# jamma.net
KiCad netlist of a schematic drawn in EAGLE
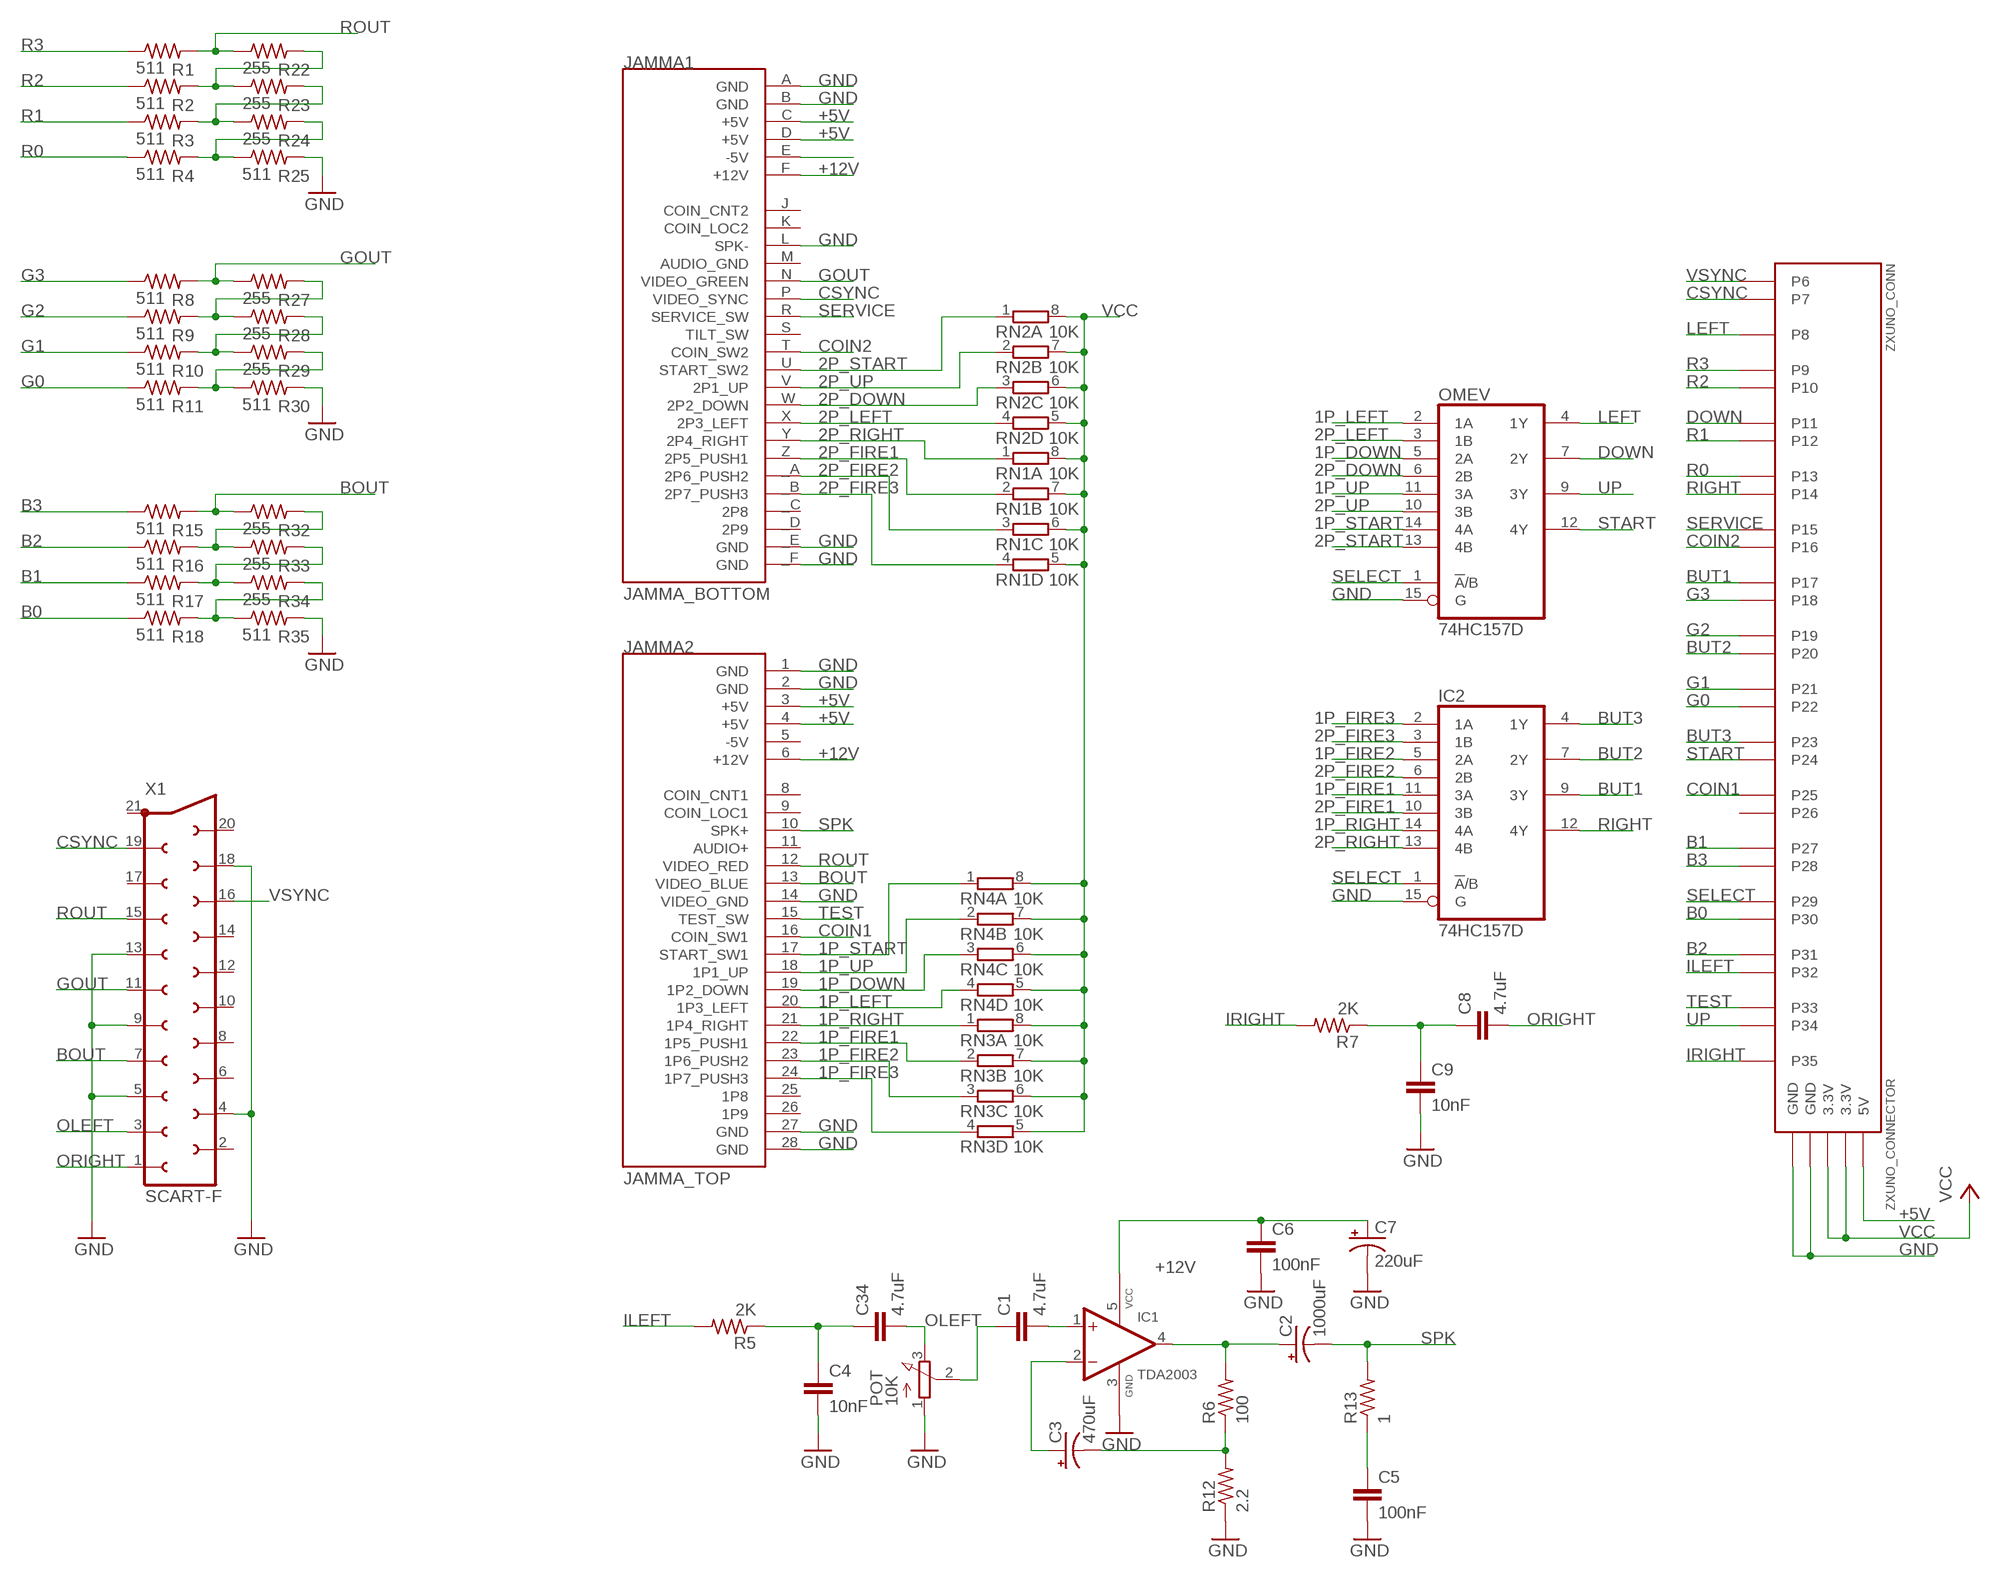
[diagram p0: schematic, sheet 1]

(export (version "E")
  (design (tool "Eeschema 10.0.6"))
  (components
    (comp (ref "C1")
      (value "4.7uF")
      (footprint "eagle-import:C0805")
      (libsource (lib "eagle-import") (part "C-EUC0805"))
    )
    (comp (ref "C2")
      (value "1000uF")
      (footprint "eagle-import:E5-13")
      (libsource (lib "eagle-import") (part "CPOL-USE5-13"))
    )
    (comp (ref "C3")
      (value "470uF")
      (footprint "eagle-import:E5-10,5")
      (libsource (lib "eagle-import") (part "CPOL-USE5-10.5"))
    )
    (comp (ref "C4")
      (value "10nF")
      (footprint "eagle-import:C0805")
      (libsource (lib "eagle-import") (part "C-EUC0805"))
    )
    (comp (ref "C5")
      (value "100nF")
      (footprint "eagle-import:C0805K")
      (libsource (lib "eagle-import") (part "C-EUC0805K"))
    )
    (comp (ref "C6")
      (value "100nF")
      (footprint "eagle-import:C0805K")
      (libsource (lib "eagle-import") (part "C-EUC0805K"))
    )
    (comp (ref "C7")
      (value "220uF")
      (footprint "eagle-import:E5-10,5")
      (libsource (lib "eagle-import") (part "CPOL-USE5-10.5"))
    )
    (comp (ref "C8")
      (value "4.7uF")
      (footprint "eagle-import:C0805")
      (libsource (lib "eagle-import") (part "C-EUC0805"))
    )
    (comp (ref "C9")
      (value "10nF")
      (footprint "eagle-import:C0805")
      (libsource (lib "eagle-import") (part "C-EUC0805"))
    )
    (comp (ref "C34")
      (value "4.7uF")
      (footprint "eagle-import:C0805")
      (libsource (lib "eagle-import") (part "C-EUC0805"))
    )
    (comp (ref "IC1")
      (value "TDA2003")
      (footprint "eagle-import:PENTAWATT-V")
      (libsource (lib "eagle-import") (part "TDA2003"))
    )
    (comp (ref "IC2")
      (value "74HC157D")
      (footprint "eagle-import:SO16")
      (libsource (lib "eagle-import") (part "74157DHC"))
    )
    (comp (ref "JAMMA1")
      (value "JAMMA_BOTTOM")
      (footprint "eagle-import:JAMMA_BOTTOM")
      (libsource (lib "eagle-import") (part "JAMMA_BOTTOM"))
    )
    (comp (ref "JAMMA2")
      (value "JAMMA_TOP")
      (footprint "eagle-import:JAMMA_TOP")
      (libsource (lib "eagle-import") (part "JAMMA_TOP"))
    )
    (comp (ref "OMEV")
      (value "74HC157D")
      (footprint "eagle-import:SO16")
      (libsource (lib "eagle-import") (part "74157DHC"))
    )
    (comp (ref "POT")
      (value "10K")
      (footprint "eagle-import:POT")
      (libsource (lib "eagle-import") (part "POT"))
    )
    (comp (ref "R1")
      (value "511")
      (footprint "eagle-import:R0805")
      (libsource (lib "eagle-import") (part "R-US_R0805"))
    )
    (comp (ref "R2")
      (value "511")
      (footprint "eagle-import:R0805")
      (libsource (lib "eagle-import") (part "R-US_R0805"))
    )
    (comp (ref "R3")
      (value "511")
      (footprint "eagle-import:R0805")
      (libsource (lib "eagle-import") (part "R-US_R0805"))
    )
    (comp (ref "R4")
      (value "511")
      (footprint "eagle-import:R0805")
      (libsource (lib "eagle-import") (part "R-US_R0805"))
    )
    (comp (ref "R5")
      (value "2K")
      (footprint "eagle-import:M0805")
      (libsource (lib "eagle-import") (part "R-US_M0805"))
    )
    (comp (ref "R6")
      (value "100")
      (footprint "eagle-import:R0805")
      (libsource (lib "eagle-import") (part "R-US_R0805"))
    )
    (comp (ref "R7")
      (value "2K")
      (footprint "eagle-import:M0805")
      (libsource (lib "eagle-import") (part "R-US_M0805"))
    )
    (comp (ref "R8")
      (value "511")
      (footprint "eagle-import:R0805")
      (libsource (lib "eagle-import") (part "R-US_R0805"))
    )
    (comp (ref "R9")
      (value "511")
      (footprint "eagle-import:R0805")
      (libsource (lib "eagle-import") (part "R-US_R0805"))
    )
    (comp (ref "R10")
      (value "511")
      (footprint "eagle-import:R0805")
      (libsource (lib "eagle-import") (part "R-US_R0805"))
    )
    (comp (ref "R11")
      (value "511")
      (footprint "eagle-import:R0805")
      (libsource (lib "eagle-import") (part "R-US_R0805"))
    )
    (comp (ref "R12")
      (value "2.2")
      (footprint "eagle-import:R0805")
      (libsource (lib "eagle-import") (part "R-US_R0805"))
    )
    (comp (ref "R13")
      (value "1")
      (footprint "eagle-import:R0805")
      (libsource (lib "eagle-import") (part "R-US_R0805"))
    )
    (comp (ref "R15")
      (value "511")
      (footprint "eagle-import:R0805")
      (libsource (lib "eagle-import") (part "R-US_R0805"))
    )
    (comp (ref "R16")
      (value "511")
      (footprint "eagle-import:R0805")
      (libsource (lib "eagle-import") (part "R-US_R0805"))
    )
    (comp (ref "R17")
      (value "511")
      (footprint "eagle-import:R0805")
      (libsource (lib "eagle-import") (part "R-US_R0805"))
    )
    (comp (ref "R18")
      (value "511")
      (footprint "eagle-import:R0805")
      (libsource (lib "eagle-import") (part "R-US_R0805"))
    )
    (comp (ref "R22")
      (value "255")
      (footprint "eagle-import:R0805")
      (libsource (lib "eagle-import") (part "R-US_R0805"))
    )
    (comp (ref "R23")
      (value "255")
      (footprint "eagle-import:R0805")
      (libsource (lib "eagle-import") (part "R-US_R0805"))
    )
    (comp (ref "R24")
      (value "255")
      (footprint "eagle-import:R0805")
      (libsource (lib "eagle-import") (part "R-US_R0805"))
    )
    (comp (ref "R25")
      (value "511")
      (footprint "eagle-import:R0805")
      (libsource (lib "eagle-import") (part "R-US_R0805"))
    )
    (comp (ref "R27")
      (value "255")
      (footprint "eagle-import:R0805")
      (libsource (lib "eagle-import") (part "R-US_R0805"))
    )
    (comp (ref "R28")
      (value "255")
      (footprint "eagle-import:R0805")
      (libsource (lib "eagle-import") (part "R-US_R0805"))
    )
    (comp (ref "R29")
      (value "255")
      (footprint "eagle-import:R0805")
      (libsource (lib "eagle-import") (part "R-US_R0805"))
    )
    (comp (ref "R30")
      (value "511")
      (footprint "eagle-import:R0805")
      (libsource (lib "eagle-import") (part "R-US_R0805"))
    )
    (comp (ref "R32")
      (value "255")
      (footprint "eagle-import:R0805")
      (libsource (lib "eagle-import") (part "R-US_R0805"))
    )
    (comp (ref "R33")
      (value "255")
      (footprint "eagle-import:R0805")
      (libsource (lib "eagle-import") (part "R-US_R0805"))
    )
    (comp (ref "R34")
      (value "255")
      (footprint "eagle-import:R0805")
      (libsource (lib "eagle-import") (part "R-US_R0805"))
    )
    (comp (ref "R35")
      (value "511")
      (footprint "eagle-import:R0805")
      (libsource (lib "eagle-import") (part "R-US_R0805"))
    )
    (comp (ref "RN1")
      (value "10K")
      (footprint "eagle-import:0603-ARC")
      (libsource (lib "eagle-import") (part "4R-N0603-ARC"))
    )
    (comp (ref "RN2")
      (value "10K")
      (footprint "eagle-import:0603-ARC")
      (libsource (lib "eagle-import") (part "4R-N0603-ARC"))
    )
    (comp (ref "RN3")
      (value "10K")
      (footprint "eagle-import:0603-ARC")
      (libsource (lib "eagle-import") (part "4R-N0603-ARC"))
    )
    (comp (ref "RN4")
      (value "10K")
      (footprint "eagle-import:0603-ARC")
      (libsource (lib "eagle-import") (part "4R-N0603-ARC"))
    )
    (comp (ref "X1")
      (value "SCART-F")
      (footprint "eagle-import:SCART-F")
      (libsource (lib "eagle-import") (part "SCART-F"))
    )
    (comp (ref "ZXUNO_CONN")
      (value "ZXUNO_CONNECTOR")
      (footprint "eagle-import:ZXUNO_CONNECTOR")
      (libsource (lib "eagle-import") (part "ZXUNO_CONNECTOR"))
    )
  )
  (nets
    (net (code "1") (name "/+5V") (class "Default")
      (node (ref "JAMMA1") (pin "C") (pinfunction "+5V_C") (pintype "power_in"))
      (node (ref "JAMMA1") (pin "D") (pinfunction "+5V_D") (pintype "power_in"))
      (node (ref "JAMMA2") (pin "3") (pinfunction "+5V_3") (pintype "power_in"))
      (node (ref "JAMMA2") (pin "4") (pinfunction "+5V_4") (pintype "power_in"))
      (node (ref "ZXUNO_CONN") (pin "5V") (pinfunction "5V_5V") (pintype "power_in"))
    )
    (net (code "2") (name "/+12V") (class "Default")
      (node (ref "C6") (pin "1") (pinfunction "1_1") (pintype "passive"))
      (node (ref "C7") (pin "+") (pinfunction "+_+") (pintype "passive"))
      (node (ref "IC1") (pin "5") (pinfunction "VCC_5") (pintype "power_in"))
      (node (ref "JAMMA1") (pin "F") (pinfunction "+12V_F") (pintype "power_in"))
      (node (ref "JAMMA2") (pin "6") (pinfunction "+12V_6") (pintype "power_in"))
    )
    (net (code "3") (name "/-5V") (class "Default")
      (node (ref "JAMMA2") (pin "5") (pinfunction "-5V_5") (pintype "power_in"))
    )
    (net (code "4") (name "/1P_DOWN") (class "Default")
      (node (ref "JAMMA2") (pin "19") (pinfunction "1P2_DOWN_19") (pintype "input"))
      (node (ref "OMEV") (pin "5") (pinfunction "2A_5") (pintype "input"))
      (node (ref "RN4") (pin "3") (pinfunction "1_3") (pintype "passive"))
    )
    (net (code "5") (name "/1P_FIRE1") (class "Default")
      (node (ref "IC2") (pin "11") (pinfunction "3A_11") (pintype "input"))
      (node (ref "JAMMA2") (pin "22") (pinfunction "1P5_PUSH1_22") (pintype "input"))
      (node (ref "RN3") (pin "2") (pinfunction "1_2") (pintype "passive"))
    )
    (net (code "6") (name "/1P_FIRE2") (class "Default")
      (node (ref "IC2") (pin "5") (pinfunction "2A_5") (pintype "input"))
      (node (ref "JAMMA2") (pin "23") (pinfunction "1P6_PUSH2_23") (pintype "input"))
      (node (ref "RN3") (pin "3") (pinfunction "1_3") (pintype "passive"))
    )
    (net (code "7") (name "/1P_FIRE3") (class "Default")
      (node (ref "IC2") (pin "2") (pinfunction "1A_2") (pintype "input"))
      (node (ref "JAMMA2") (pin "24") (pinfunction "1P7_PUSH3_24") (pintype "input"))
      (node (ref "RN3") (pin "4") (pinfunction "1_4") (pintype "passive"))
    )
    (net (code "8") (name "/1P_LEFT") (class "Default")
      (node (ref "JAMMA2") (pin "20") (pinfunction "1P3_LEFT_20") (pintype "input"))
      (node (ref "OMEV") (pin "2") (pinfunction "1A_2") (pintype "input"))
      (node (ref "RN4") (pin "4") (pinfunction "1_4") (pintype "passive"))
    )
    (net (code "9") (name "/1P_RIGHT") (class "Default")
      (node (ref "IC2") (pin "14") (pinfunction "4A_14") (pintype "input"))
      (node (ref "JAMMA2") (pin "21") (pinfunction "1P4_RIGHT_21") (pintype "input"))
      (node (ref "RN3") (pin "1") (pinfunction "1_1") (pintype "passive"))
    )
    (net (code "10") (name "/1P_START") (class "Default")
      (node (ref "JAMMA2") (pin "17") (pinfunction "START_SW1_17") (pintype "input"))
      (node (ref "OMEV") (pin "14") (pinfunction "4A_14") (pintype "input"))
      (node (ref "RN4") (pin "1") (pinfunction "1_1") (pintype "passive"))
    )
    (net (code "11") (name "/1P_UP") (class "Default")
      (node (ref "JAMMA2") (pin "18") (pinfunction "1P1_UP_18") (pintype "input"))
      (node (ref "OMEV") (pin "11") (pinfunction "3A_11") (pintype "input"))
      (node (ref "RN4") (pin "2") (pinfunction "1_2") (pintype "passive"))
    )
    (net (code "12") (name "/2P_DOWN") (class "Default")
      (node (ref "JAMMA1") (pin "W") (pinfunction "2P2_DOWN_W") (pintype "input"))
      (node (ref "OMEV") (pin "6") (pinfunction "2B_6") (pintype "input"))
      (node (ref "RN2") (pin "3") (pinfunction "1_3") (pintype "passive"))
    )
    (net (code "13") (name "/2P_FIRE1") (class "Default")
      (node (ref "IC2") (pin "10") (pinfunction "3B_10") (pintype "input"))
      (node (ref "JAMMA1") (pin "Z") (pinfunction "2P5_PUSH1_Z") (pintype "input"))
      (node (ref "RN1") (pin "2") (pinfunction "1_2") (pintype "passive"))
    )
    (net (code "14") (name "/2P_FIRE2") (class "Default")
      (node (ref "IC2") (pin "6") (pinfunction "2B_6") (pintype "input"))
      (node (ref "JAMMA1") (pin "_A") (pinfunction "2P6_PUSH2__A") (pintype "input"))
      (node (ref "RN1") (pin "3") (pinfunction "1_3") (pintype "passive"))
    )
    (net (code "15") (name "/2P_FIRE3") (class "Default")
      (node (ref "IC2") (pin "3") (pinfunction "1B_3") (pintype "input"))
      (node (ref "JAMMA1") (pin "_B") (pinfunction "2P7_PUSH3__B") (pintype "input"))
      (node (ref "RN1") (pin "4") (pinfunction "1_4") (pintype "passive"))
    )
    (net (code "16") (name "/2P_LEFT") (class "Default")
      (node (ref "JAMMA1") (pin "X") (pinfunction "2P3_LEFT_X") (pintype "input"))
      (node (ref "OMEV") (pin "3") (pinfunction "1B_3") (pintype "input"))
      (node (ref "RN2") (pin "4") (pinfunction "1_4") (pintype "passive"))
    )
    (net (code "17") (name "/2P_RIGHT") (class "Default")
      (node (ref "IC2") (pin "13") (pinfunction "4B_13") (pintype "input"))
      (node (ref "JAMMA1") (pin "Y") (pinfunction "2P4_RIGHT_Y") (pintype "input"))
      (node (ref "RN1") (pin "1") (pinfunction "1_1") (pintype "passive"))
    )
    (net (code "18") (name "/2P_START") (class "Default")
      (node (ref "JAMMA1") (pin "U") (pinfunction "START_SW2_U") (pintype "input"))
      (node (ref "OMEV") (pin "13") (pinfunction "4B_13") (pintype "input"))
      (node (ref "RN2") (pin "1") (pinfunction "1_1") (pintype "passive"))
    )
    (net (code "19") (name "/2P_UP") (class "Default")
      (node (ref "JAMMA1") (pin "V") (pinfunction "2P1_UP_V") (pintype "input"))
      (node (ref "OMEV") (pin "10") (pinfunction "3B_10") (pintype "input"))
      (node (ref "RN2") (pin "2") (pinfunction "1_2") (pintype "passive"))
    )
    (net (code "20") (name "/B0") (class "Default")
      (node (ref "R18") (pin "1") (pinfunction "1_1") (pintype "passive"))
      (node (ref "ZXUNO_CONN") (pin "P30") (pinfunction "P30_P30") (pintype "bidirectional"))
    )
    (net (code "21") (name "/B1") (class "Default")
      (node (ref "R17") (pin "1") (pinfunction "1_1") (pintype "passive"))
      (node (ref "ZXUNO_CONN") (pin "P27") (pinfunction "P27_P27") (pintype "bidirectional"))
    )
    (net (code "22") (name "/B2") (class "Default")
      (node (ref "R16") (pin "1") (pinfunction "1_1") (pintype "passive"))
      (node (ref "ZXUNO_CONN") (pin "P31") (pinfunction "P31_P31") (pintype "bidirectional"))
    )
    (net (code "23") (name "/B3") (class "Default")
      (node (ref "R15") (pin "1") (pinfunction "1_1") (pintype "passive"))
      (node (ref "ZXUNO_CONN") (pin "P28") (pinfunction "P28_P28") (pintype "bidirectional"))
    )
    (net (code "24") (name "/BOUT") (class "Default")
      (node (ref "JAMMA2") (pin "13") (pinfunction "VIDEO_BLUE_13") (pintype "output"))
      (node (ref "R15") (pin "2") (pinfunction "2_2") (pintype "passive"))
      (node (ref "R32") (pin "1") (pinfunction "1_1") (pintype "passive"))
      (node (ref "X1") (pin "7") (pinfunction "7_7") (pintype "passive"))
    )
    (net (code "25") (name "/BUT1") (class "Default")
      (node (ref "IC2") (pin "9") (pinfunction "3Y_9") (pintype "output"))
      (node (ref "ZXUNO_CONN") (pin "P17") (pinfunction "P17_P17") (pintype "bidirectional"))
    )
    (net (code "26") (name "/BUT2") (class "Default")
      (node (ref "IC2") (pin "7") (pinfunction "2Y_7") (pintype "output"))
      (node (ref "ZXUNO_CONN") (pin "P20") (pinfunction "P20_P20") (pintype "bidirectional"))
    )
    (net (code "27") (name "/BUT3") (class "Default")
      (node (ref "IC2") (pin "4") (pinfunction "1Y_4") (pintype "output"))
      (node (ref "ZXUNO_CONN") (pin "P23") (pinfunction "P23_P23") (pintype "bidirectional"))
    )
    (net (code "28") (name "/COIN1") (class "Default")
      (node (ref "JAMMA2") (pin "16") (pinfunction "COIN_SW1_16") (pintype "input"))
      (node (ref "ZXUNO_CONN") (pin "P25") (pinfunction "P25_P25") (pintype "bidirectional"))
    )
    (net (code "29") (name "/COIN2") (class "Default")
      (node (ref "JAMMA1") (pin "T") (pinfunction "COIN_SW2_T") (pintype "input"))
      (node (ref "ZXUNO_CONN") (pin "P16") (pinfunction "P16_P16") (pintype "bidirectional"))
    )
    (net (code "30") (name "/CSYNC") (class "Default")
      (node (ref "JAMMA1") (pin "P") (pinfunction "VIDEO_SYNC_P") (pintype "output"))
      (node (ref "X1") (pin "19") (pinfunction "19_19") (pintype "passive"))
      (node (ref "ZXUNO_CONN") (pin "P7") (pinfunction "P7_P7") (pintype "bidirectional"))
    )
    (net (code "31") (name "/DOWN") (class "Default")
      (node (ref "OMEV") (pin "7") (pinfunction "2Y_7") (pintype "output"))
      (node (ref "ZXUNO_CONN") (pin "P11") (pinfunction "P11_P11") (pintype "bidirectional"))
    )
    (net (code "32") (name "/G0") (class "Default")
      (node (ref "R11") (pin "1") (pinfunction "1_1") (pintype "passive"))
      (node (ref "ZXUNO_CONN") (pin "P22") (pinfunction "P22_P22") (pintype "bidirectional"))
    )
    (net (code "33") (name "/G1") (class "Default")
      (node (ref "R10") (pin "1") (pinfunction "1_1") (pintype "passive"))
      (node (ref "ZXUNO_CONN") (pin "P21") (pinfunction "P21_P21") (pintype "bidirectional"))
    )
    (net (code "34") (name "/G2") (class "Default")
      (node (ref "R9") (pin "1") (pinfunction "1_1") (pintype "passive"))
      (node (ref "ZXUNO_CONN") (pin "P19") (pinfunction "P19_P19") (pintype "bidirectional"))
    )
    (net (code "35") (name "/G3") (class "Default")
      (node (ref "R8") (pin "1") (pinfunction "1_1") (pintype "passive"))
      (node (ref "ZXUNO_CONN") (pin "P18") (pinfunction "P18_P18") (pintype "bidirectional"))
    )
    (net (code "36") (name "/GOUT") (class "Default")
      (node (ref "JAMMA1") (pin "N") (pinfunction "VIDEO_GREEN_N") (pintype "output"))
      (node (ref "R27") (pin "1") (pinfunction "1_1") (pintype "passive"))
      (node (ref "R8") (pin "2") (pinfunction "2_2") (pintype "passive"))
      (node (ref "X1") (pin "11") (pinfunction "11_11") (pintype "passive"))
    )
    (net (code "37") (name "/ILEFT") (class "Default")
      (node (ref "R5") (pin "2") (pinfunction "2_2") (pintype "passive"))
      (node (ref "ZXUNO_CONN") (pin "P32") (pinfunction "P32_P32") (pintype "bidirectional"))
    )
    (net (code "38") (name "/IRIGHT") (class "Default")
      (node (ref "R7") (pin "2") (pinfunction "2_2") (pintype "passive"))
      (node (ref "ZXUNO_CONN") (pin "P35") (pinfunction "P35_P35") (pintype "bidirectional"))
    )
    (net (code "39") (name "/LEFT") (class "Default")
      (node (ref "OMEV") (pin "4") (pinfunction "1Y_4") (pintype "output"))
      (node (ref "ZXUNO_CONN") (pin "P8") (pinfunction "P8_P8") (pintype "bidirectional"))
    )
    (net (code "40") (name "/OLEFT") (class "Default")
      (node (ref "C34") (pin "2") (pinfunction "2_2") (pintype "passive"))
      (node (ref "POT") (pin "3") (pinfunction "E_3") (pintype "passive"))
      (node (ref "X1") (pin "3") (pinfunction "3_3") (pintype "passive"))
    )
    (net (code "41") (name "/ORIGHT") (class "Default")
      (node (ref "C8") (pin "2") (pinfunction "2_2") (pintype "passive"))
      (node (ref "X1") (pin "1") (pinfunction "1_1") (pintype "passive"))
    )
    (net (code "42") (name "/R0") (class "Default")
      (node (ref "R4") (pin "1") (pinfunction "1_1") (pintype "passive"))
      (node (ref "ZXUNO_CONN") (pin "P13") (pinfunction "P13_P13") (pintype "bidirectional"))
    )
    (net (code "43") (name "/R1") (class "Default")
      (node (ref "R3") (pin "1") (pinfunction "1_1") (pintype "passive"))
      (node (ref "ZXUNO_CONN") (pin "P12") (pinfunction "P12_P12") (pintype "bidirectional"))
    )
    (net (code "44") (name "/R2") (class "Default")
      (node (ref "R2") (pin "1") (pinfunction "1_1") (pintype "passive"))
      (node (ref "ZXUNO_CONN") (pin "P10") (pinfunction "P10_P10") (pintype "bidirectional"))
    )
    (net (code "45") (name "/R3") (class "Default")
      (node (ref "R1") (pin "1") (pinfunction "1_1") (pintype "passive"))
      (node (ref "ZXUNO_CONN") (pin "P9") (pinfunction "P9_P9") (pintype "bidirectional"))
    )
    (net (code "46") (name "/RIGHT") (class "Default")
      (node (ref "IC2") (pin "12") (pinfunction "4Y_12") (pintype "output"))
      (node (ref "ZXUNO_CONN") (pin "P14") (pinfunction "P14_P14") (pintype "bidirectional"))
    )
    (net (code "47") (name "/ROUT") (class "Default")
      (node (ref "JAMMA2") (pin "12") (pinfunction "VIDEO_RED_12") (pintype "output"))
      (node (ref "R1") (pin "2") (pinfunction "2_2") (pintype "passive"))
      (node (ref "R22") (pin "1") (pinfunction "1_1") (pintype "passive"))
      (node (ref "X1") (pin "15") (pinfunction "15_15") (pintype "passive"))
    )
    (net (code "48") (name "/SELECT") (class "Default")
      (node (ref "IC2") (pin "1") (pinfunction "~{A}/B_1") (pintype "input"))
      (node (ref "OMEV") (pin "1") (pinfunction "~{A}/B_1") (pintype "input"))
      (node (ref "ZXUNO_CONN") (pin "P29") (pinfunction "P29_P29") (pintype "bidirectional"))
    )
    (net (code "49") (name "/SERVICE") (class "Default")
      (node (ref "JAMMA1") (pin "R") (pinfunction "SERVICE_SW_R") (pintype "input"))
      (node (ref "ZXUNO_CONN") (pin "P15") (pinfunction "P15_P15") (pintype "bidirectional"))
    )
    (net (code "50") (name "/SPK") (class "Default")
      (node (ref "C2") (pin "-") (pinfunction "-_-") (pintype "passive"))
      (node (ref "JAMMA2") (pin "10") (pinfunction "SPK+_10") (pintype "output"))
      (node (ref "R13") (pin "2") (pinfunction "2_2") (pintype "passive"))
    )
    (net (code "51") (name "/START") (class "Default")
      (node (ref "OMEV") (pin "12") (pinfunction "4Y_12") (pintype "output"))
      (node (ref "ZXUNO_CONN") (pin "P24") (pinfunction "P24_P24") (pintype "bidirectional"))
    )
    (net (code "52") (name "/TEST") (class "Default")
      (node (ref "JAMMA2") (pin "15") (pinfunction "TEST_SW_15") (pintype "input"))
      (node (ref "ZXUNO_CONN") (pin "P33") (pinfunction "P33_P33") (pintype "bidirectional"))
    )
    (net (code "53") (name "/UP") (class "Default")
      (node (ref "OMEV") (pin "9") (pinfunction "3Y_9") (pintype "output"))
      (node (ref "ZXUNO_CONN") (pin "P34") (pinfunction "P34_P34") (pintype "bidirectional"))
    )
    (net (code "54") (name "/VSYNC") (class "Default")
      (node (ref "X1") (pin "16") (pinfunction "16_16") (pintype "passive"))
      (node (ref "ZXUNO_CONN") (pin "P6") (pinfunction "P6_P6") (pintype "bidirectional"))
    )
    (net (code "55") (name "GND") (class "Default")
      (node (ref "C4") (pin "2") (pinfunction "2_2") (pintype "passive"))
      (node (ref "C5") (pin "2") (pinfunction "2_2") (pintype "passive"))
      (node (ref "C6") (pin "2") (pinfunction "2_2") (pintype "passive"))
      (node (ref "C7") (pin "-") (pinfunction "-_-") (pintype "passive"))
      (node (ref "C9") (pin "2") (pinfunction "2_2") (pintype "passive"))
      (node (ref "IC1") (pin "3") (pinfunction "GND_3") (pintype "power_in"))
      (node (ref "IC2") (pin "15") (pinfunction "G_15") (pintype "input"))
      (node (ref "JAMMA1") (pin "A") (pinfunction "GND_A") (pintype "power_in"))
      (node (ref "JAMMA1") (pin "B") (pinfunction "GND_B") (pintype "power_in"))
      (node (ref "JAMMA1") (pin "L") (pinfunction "SPK-_L") (pintype "output"))
      (node (ref "JAMMA1") (pin "_E") (pinfunction "GND__E") (pintype "power_in"))
      (node (ref "JAMMA1") (pin "_F") (pinfunction "GND__F") (pintype "power_in"))
      (node (ref "JAMMA2") (pin "1") (pinfunction "GND_1") (pintype "power_in"))
      (node (ref "JAMMA2") (pin "14") (pinfunction "VIDEO_GND_14") (pintype "output"))
      (node (ref "JAMMA2") (pin "2") (pinfunction "GND_2") (pintype "power_in"))
      (node (ref "JAMMA2") (pin "27") (pinfunction "GND_27") (pintype "power_in"))
      (node (ref "JAMMA2") (pin "28") (pinfunction "GND_28") (pintype "power_in"))
      (node (ref "OMEV") (pin "15") (pinfunction "G_15") (pintype "input"))
      (node (ref "POT") (pin "1") (pinfunction "A_1") (pintype "passive"))
      (node (ref "R12") (pin "1") (pinfunction "1_1") (pintype "passive"))
      (node (ref "R25") (pin "2") (pinfunction "2_2") (pintype "passive"))
      (node (ref "R30") (pin "2") (pinfunction "2_2") (pintype "passive"))
      (node (ref "R35") (pin "2") (pinfunction "2_2") (pintype "passive"))
      (node (ref "X1") (pin "13") (pinfunction "13_13") (pintype "passive"))
      (node (ref "X1") (pin "18") (pinfunction "18_18") (pintype "passive"))
      (node (ref "X1") (pin "4") (pinfunction "4_4") (pintype "passive"))
      (node (ref "X1") (pin "5") (pinfunction "5_5") (pintype "passive"))
      (node (ref "X1") (pin "9") (pinfunction "9_9") (pintype "passive"))
      (node (ref "ZXUNO_CONN") (pin "GND@1") (pinfunction "GND_GND@1") (pintype "power_in"))
      (node (ref "ZXUNO_CONN") (pin "GND@2") (pinfunction "GND_GND@2") (pintype "power_in"))
    )
    (net (code "56") (name "Net-(C3-Pad-)") (class "Default")
      (node (ref "C3") (pin "-") (pinfunction "-_-") (pintype "passive"))
      (node (ref "R12") (pin "2") (pinfunction "2_2") (pintype "passive"))
      (node (ref "R6") (pin "1") (pinfunction "1_1") (pintype "passive"))
    )
    (net (code "57") (name "Net-(C5-Pad1)") (class "Default")
      (node (ref "C5") (pin "1") (pinfunction "1_1") (pintype "passive"))
      (node (ref "R13") (pin "1") (pinfunction "1_1") (pintype "passive"))
    )
    (net (code "58") (name "Net-(C8-Pad1)") (class "Default")
      (node (ref "C8") (pin "1") (pinfunction "1_1") (pintype "passive"))
      (node (ref "C9") (pin "1") (pinfunction "1_1") (pintype "passive"))
      (node (ref "R7") (pin "1") (pinfunction "1_1") (pintype "passive"))
    )
    (net (code "59") (name "Net-(C34-Pad1)") (class "Default")
      (node (ref "C34") (pin "1") (pinfunction "1_1") (pintype "passive"))
      (node (ref "C4") (pin "1") (pinfunction "1_1") (pintype "passive"))
      (node (ref "R5") (pin "1") (pinfunction "1_1") (pintype "passive"))
    )
    (net (code "60") (name "Net-(IC1-+IN)") (class "Default")
      (node (ref "C1") (pin "2") (pinfunction "2_2") (pintype "passive"))
      (node (ref "IC1") (pin "1") (pinfunction "+IN_1") (pintype "input"))
    )
    (net (code "61") (name "Net-(IC1--IN)") (class "Default")
      (node (ref "C3") (pin "+") (pinfunction "+_+") (pintype "passive"))
      (node (ref "IC1") (pin "2") (pinfunction "-IN_2") (pintype "input"))
    )
    (net (code "62") (name "Net-(IC1-OUT)") (class "Default")
      (node (ref "C2") (pin "+") (pinfunction "+_+") (pintype "passive"))
      (node (ref "IC1") (pin "4") (pinfunction "OUT_4") (pintype "output"))
      (node (ref "R6") (pin "2") (pinfunction "2_2") (pintype "passive"))
    )
    (net (code "63") (name "Net-(POT-S)") (class "Default")
      (node (ref "C1") (pin "1") (pinfunction "1_1") (pintype "passive"))
      (node (ref "POT") (pin "2") (pinfunction "S_2") (pintype "passive"))
    )
    (net (code "64") (name "Net-(R2-Pad2)") (class "Default")
      (node (ref "R2") (pin "2") (pinfunction "2_2") (pintype "passive"))
      (node (ref "R22") (pin "2") (pinfunction "2_2") (pintype "passive"))
      (node (ref "R23") (pin "1") (pinfunction "1_1") (pintype "passive"))
    )
    (net (code "65") (name "Net-(R10-Pad2)") (class "Default")
      (node (ref "R10") (pin "2") (pinfunction "2_2") (pintype "passive"))
      (node (ref "R28") (pin "2") (pinfunction "2_2") (pintype "passive"))
      (node (ref "R29") (pin "1") (pinfunction "1_1") (pintype "passive"))
    )
    (net (code "66") (name "Net-(R11-Pad2)") (class "Default")
      (node (ref "R11") (pin "2") (pinfunction "2_2") (pintype "passive"))
      (node (ref "R29") (pin "2") (pinfunction "2_2") (pintype "passive"))
      (node (ref "R30") (pin "1") (pinfunction "1_1") (pintype "passive"))
    )
    (net (code "67") (name "Net-(R16-Pad2)") (class "Default")
      (node (ref "R16") (pin "2") (pinfunction "2_2") (pintype "passive"))
      (node (ref "R32") (pin "2") (pinfunction "2_2") (pintype "passive"))
      (node (ref "R33") (pin "1") (pinfunction "1_1") (pintype "passive"))
    )
    (net (code "68") (name "Net-(R17-Pad2)") (class "Default")
      (node (ref "R17") (pin "2") (pinfunction "2_2") (pintype "passive"))
      (node (ref "R33") (pin "2") (pinfunction "2_2") (pintype "passive"))
      (node (ref "R34") (pin "1") (pinfunction "1_1") (pintype "passive"))
    )
    (net (code "69") (name "Net-(R18-Pad2)") (class "Default")
      (node (ref "R18") (pin "2") (pinfunction "2_2") (pintype "passive"))
      (node (ref "R34") (pin "2") (pinfunction "2_2") (pintype "passive"))
      (node (ref "R35") (pin "1") (pinfunction "1_1") (pintype "passive"))
    )
    (net (code "70") (name "Net-(R23-Pad2)") (class "Default")
      (node (ref "R23") (pin "2") (pinfunction "2_2") (pintype "passive"))
      (node (ref "R24") (pin "1") (pinfunction "1_1") (pintype "passive"))
      (node (ref "R3") (pin "2") (pinfunction "2_2") (pintype "passive"))
    )
    (net (code "71") (name "Net-(R24-Pad2)") (class "Default")
      (node (ref "R24") (pin "2") (pinfunction "2_2") (pintype "passive"))
      (node (ref "R25") (pin "1") (pinfunction "1_1") (pintype "passive"))
      (node (ref "R4") (pin "2") (pinfunction "2_2") (pintype "passive"))
    )
    (net (code "72") (name "Net-(R27-Pad2)") (class "Default")
      (node (ref "R27") (pin "2") (pinfunction "2_2") (pintype "passive"))
      (node (ref "R28") (pin "1") (pinfunction "1_1") (pintype "passive"))
      (node (ref "R9") (pin "2") (pinfunction "2_2") (pintype "passive"))
    )
    (net (code "73") (name "VCC") (class "Default")
      (node (ref "RN1") (pin "5") (pinfunction "2_5") (pintype "passive"))
      (node (ref "RN1") (pin "6") (pinfunction "2_6") (pintype "passive"))
      (node (ref "RN1") (pin "7") (pinfunction "2_7") (pintype "passive"))
      (node (ref "RN1") (pin "8") (pinfunction "2_8") (pintype "passive"))
      (node (ref "RN2") (pin "5") (pinfunction "2_5") (pintype "passive"))
      (node (ref "RN2") (pin "6") (pinfunction "2_6") (pintype "passive"))
      (node (ref "RN2") (pin "7") (pinfunction "2_7") (pintype "passive"))
      (node (ref "RN2") (pin "8") (pinfunction "2_8") (pintype "passive"))
      (node (ref "RN3") (pin "5") (pinfunction "2_5") (pintype "passive"))
      (node (ref "RN3") (pin "6") (pinfunction "2_6") (pintype "passive"))
      (node (ref "RN3") (pin "7") (pinfunction "2_7") (pintype "passive"))
      (node (ref "RN3") (pin "8") (pinfunction "2_8") (pintype "passive"))
      (node (ref "RN4") (pin "5") (pinfunction "2_5") (pintype "passive"))
      (node (ref "RN4") (pin "6") (pinfunction "2_6") (pintype "passive"))
      (node (ref "RN4") (pin "7") (pinfunction "2_7") (pintype "passive"))
      (node (ref "RN4") (pin "8") (pinfunction "2_8") (pintype "passive"))
      (node (ref "ZXUNO_CONN") (pin "3.3V@1") (pinfunction "3.3V_3.3V@1") (pintype "power_in"))
      (node (ref "ZXUNO_CONN") (pin "3.3V@2") (pinfunction "3.3V_3.3V@2") (pintype "power_in"))
    )
    (net (code "74") (name "unconnected-(JAMMA1--5V-PadE)") (class "Default")
      (node (ref "JAMMA1") (pin "E") (pinfunction "-5V_E") (pintype "power_in"))
    )
    (net (code "75") (name "unconnected-(JAMMA1-2P8-Pad_C)") (class "Default")
      (node (ref "JAMMA1") (pin "_C") (pinfunction "2P8__C") (pintype "input"))
    )
    (net (code "76") (name "unconnected-(JAMMA1-2P9-Pad_D)") (class "Default")
      (node (ref "JAMMA1") (pin "_D") (pinfunction "2P9__D") (pintype "input"))
    )
    (net (code "77") (name "unconnected-(JAMMA1-AUDIO_GND-PadM)") (class "Default")
      (node (ref "JAMMA1") (pin "M") (pinfunction "AUDIO_GND_M") (pintype "output"))
    )
    (net (code "78") (name "unconnected-(JAMMA1-COIN_CNT2-PadJ)") (class "Default")
      (node (ref "JAMMA1") (pin "J") (pinfunction "COIN_CNT2_J") (pintype "output"))
    )
    (net (code "79") (name "unconnected-(JAMMA1-COIN_LOC2-PadK)") (class "Default")
      (node (ref "JAMMA1") (pin "K") (pinfunction "COIN_LOC2_K") (pintype "output"))
    )
    (net (code "80") (name "unconnected-(JAMMA1-TILT_SW-PadS)") (class "Default")
      (node (ref "JAMMA1") (pin "S") (pinfunction "TILT_SW_S") (pintype "input"))
    )
    (net (code "81") (name "unconnected-(JAMMA2-1P8-Pad25)") (class "Default")
      (node (ref "JAMMA2") (pin "25") (pinfunction "1P8_25") (pintype "input"))
    )
    (net (code "82") (name "unconnected-(JAMMA2-1P9-Pad26)") (class "Default")
      (node (ref "JAMMA2") (pin "26") (pinfunction "1P9_26") (pintype "input"))
    )
    (net (code "83") (name "unconnected-(JAMMA2-AUDIO+-Pad11)") (class "Default")
      (node (ref "JAMMA2") (pin "11") (pinfunction "AUDIO+_11") (pintype "output"))
    )
    (net (code "84") (name "unconnected-(JAMMA2-COIN_CNT1-Pad8)") (class "Default")
      (node (ref "JAMMA2") (pin "8") (pinfunction "COIN_CNT1_8") (pintype "output"))
    )
    (net (code "85") (name "unconnected-(JAMMA2-COIN_LOC1-Pad9)") (class "Default")
      (node (ref "JAMMA2") (pin "9") (pinfunction "COIN_LOC1_9") (pintype "output"))
    )
    (net (code "86") (name "unconnected-(X1-Pad2)") (class "Default")
      (node (ref "X1") (pin "2") (pinfunction "2_2") (pintype "passive"))
    )
    (net (code "87") (name "unconnected-(X1-Pad6)") (class "Default")
      (node (ref "X1") (pin "6") (pinfunction "6_6") (pintype "passive"))
    )
    (net (code "88") (name "unconnected-(X1-Pad8)") (class "Default")
      (node (ref "X1") (pin "8") (pinfunction "8_8") (pintype "passive"))
    )
    (net (code "89") (name "unconnected-(X1-Pad10)") (class "Default")
      (node (ref "X1") (pin "10") (pinfunction "10_10") (pintype "passive"))
    )
    (net (code "90") (name "unconnected-(X1-Pad12)") (class "Default")
      (node (ref "X1") (pin "12") (pinfunction "12_12") (pintype "passive"))
    )
    (net (code "91") (name "unconnected-(X1-Pad14)") (class "Default")
      (node (ref "X1") (pin "14") (pinfunction "14_14") (pintype "passive"))
    )
    (net (code "92") (name "unconnected-(X1-Pad17)") (class "Default")
      (node (ref "X1") (pin "17") (pinfunction "17_17") (pintype "passive"))
    )
    (net (code "93") (name "unconnected-(X1-Pad20)") (class "Default")
      (node (ref "X1") (pin "20") (pinfunction "20_20") (pintype "passive"))
    )
    (net (code "94") (name "unconnected-(X1-Pad21)") (class "Default")
      (node (ref "X1") (pin "21") (pinfunction "21_21") (pintype "passive"))
    )
    (net (code "95") (name "unconnected-(ZXUNO_CONN-PadP26)") (class "Default")
      (node (ref "ZXUNO_CONN") (pin "P26") (pinfunction "P26_P26") (pintype "bidirectional"))
    )
  )
)
